# PWR_supply_sch.net
KiCad netlist of a schematic drawn in Altium Designer
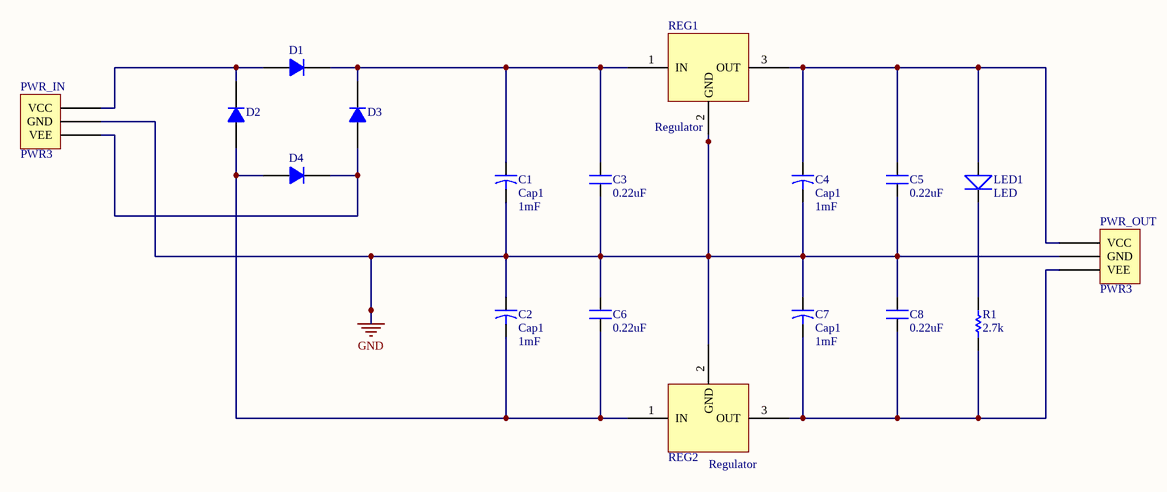
[diagram p0: PWR_supply_sch.SchDoc]

(export (version "E")
  (design (tool "Eeschema 10.0.6"))
  (components
    (comp (ref "C1")
      (value "Cap1")
      (footprint "CAP1")
      (description "Capacitor")
      (fields (field (name "ALTIUM_VALUE") "1mF") (field (name "PUBLISHER") "Altium Limited"))
      (libsource (lib "Common Parts") (part "Cap1"))
    )
    (comp (ref "C2")
      (value "Cap1")
      (footprint "CAP1")
      (description "Capacitor")
      (fields (field (name "ALTIUM_VALUE") "1mF") (field (name "PUBLISHER") "Altium Limited"))
      (libsource (lib "Common Parts") (part "Cap1"))
    )
    (comp (ref "C3")
      (value "0.22uF")
      (footprint "CAP3")
      (description "Capacitor")
      (fields (field (name "Comment") "Cap3") (field (name "PUBLISHER") "Altium Limited"))
      (libsource (lib "Common Parts") (part "Cap3"))
    )
    (comp (ref "C4")
      (value "Cap1")
      (footprint "CAP1")
      (description "Capacitor")
      (fields (field (name "ALTIUM_VALUE") "1mF") (field (name "PUBLISHER") "Altium Limited"))
      (libsource (lib "Common Parts") (part "Cap1"))
    )
    (comp (ref "C5")
      (value "0.22uF")
      (footprint "CAP3")
      (description "Capacitor")
      (fields (field (name "Comment") "Cap3") (field (name "PUBLISHER") "Altium Limited"))
      (libsource (lib "Common Parts") (part "Cap3"))
    )
    (comp (ref "C6")
      (value "0.22uF")
      (footprint "CAP3")
      (description "Capacitor")
      (fields (field (name "Comment") "Cap3") (field (name "PUBLISHER") "Altium Limited"))
      (libsource (lib "Common Parts") (part "Cap3"))
    )
    (comp (ref "C7")
      (value "Cap1")
      (footprint "CAP1")
      (description "Capacitor")
      (fields (field (name "ALTIUM_VALUE") "1mF") (field (name "PUBLISHER") "Altium Limited"))
      (libsource (lib "Common Parts") (part "Cap1"))
    )
    (comp (ref "C8")
      (value "0.22uF")
      (footprint "CAP3")
      (description "Capacitor")
      (fields (field (name "Comment") "Cap3") (field (name "PUBLISHER") "Altium Limited"))
      (libsource (lib "Common Parts") (part "Cap3"))
    )
    (comp (ref "D1")
      (value "1N4007")
      (footprint "1N4007")
      (description "1 Amp General Purpose Rectifier")
      (fields (field (name "PUBLISHER") "Altium Limited"))
      (libsource (lib "Common Parts") (part "1N4007"))
    )
    (comp (ref "D2")
      (value "1N4007")
      (footprint "1N4007")
      (description "1 Amp General Purpose Rectifier")
      (fields (field (name "PUBLISHER") "Altium Limited"))
      (libsource (lib "Common Parts") (part "1N4007"))
    )
    (comp (ref "D3")
      (value "1N4007")
      (footprint "1N4007")
      (description "1 Amp General Purpose Rectifier")
      (fields (field (name "PUBLISHER") "Altium Limited"))
      (libsource (lib "Common Parts") (part "1N4007"))
    )
    (comp (ref "D4")
      (value "1N4007")
      (footprint "1N4007")
      (description "1 Amp General Purpose Rectifier")
      (fields (field (name "PUBLISHER") "Altium Limited"))
      (libsource (lib "Common Parts") (part "1N4007"))
    )
    (comp (ref "LED1") (value "LED") (footprint "LED") (libsource (lib "Common Parts") (part "LED")))
    (comp (ref "PWR_IN") (value "PWR3") (footprint "PWR3") (libsource (lib "") (part "PWR3_1")))
    (comp (ref "PWR_OUT") (value "PWR3") (footprint "PWR3") (libsource (lib "Common Parts") (part "PWR3")))
    (comp (ref "R1")
      (value "2.7k")
      (footprint "RES_TOP_1")
      (description "Resistor")
      (fields (field (name "Comment") "Res1") (field (name "PUBLISHER") "Altium Limited"))
      (libsource (lib "Common Parts") (part "Res1"))
    )
    (comp (ref "REG1") (value "Regulator") (footprint "Regulator") (libsource (lib "") (part "Regulator_1")))
    (comp (ref "REG2")
      (value "Regulator")
      (footprint "Regulator")
      (libsource (lib "Common Parts") (part "Regulator"))
    )
  )
  (nets
    (net (code "1") (name "GND") (class "Default")
      (node (ref "C1") (pin "2") (pinfunction "2_2") (pintype "passive"))
      (node (ref "C2") (pin "1") (pinfunction "1_1") (pintype "passive"))
      (node (ref "C3") (pin "1") (pinfunction "1_1") (pintype "passive"))
      (node (ref "C4") (pin "2") (pinfunction "2_2") (pintype "passive"))
      (node (ref "C5") (pin "1") (pinfunction "1_1") (pintype "passive"))
      (node (ref "C6") (pin "2") (pinfunction "2_2") (pintype "passive"))
      (node (ref "C7") (pin "1") (pinfunction "1_1") (pintype "passive"))
      (node (ref "C8") (pin "2") (pinfunction "2_2") (pintype "passive"))
      (node (ref "PWR_IN") (pin "2") (pinfunction "GND_2") (pintype "passive"))
      (node (ref "PWR_OUT") (pin "2") (pinfunction "GND_2") (pintype "passive"))
      (node (ref "REG1") (pin "2") (pinfunction "GND_2") (pintype "passive"))
      (node (ref "REG2") (pin "2") (pinfunction "GND_2") (pintype "passive"))
    )
    (net (code "2") (name "Net-(D1-A)") (class "Default")
      (node (ref "D1") (pin "1") (pinfunction "A_1") (pintype "passive"))
      (node (ref "D2") (pin "2") (pinfunction "K_2") (pintype "passive"))
      (node (ref "PWR_IN") (pin "1") (pinfunction "VCC_1") (pintype "passive"))
    )
    (net (code "3") (name "Net-(D1-K)") (class "Default")
      (node (ref "C1") (pin "1") (pinfunction "1_1") (pintype "passive"))
      (node (ref "C3") (pin "2") (pinfunction "2_2") (pintype "passive"))
      (node (ref "D1") (pin "2") (pinfunction "K_2") (pintype "passive"))
      (node (ref "D3") (pin "2") (pinfunction "K_2") (pintype "passive"))
      (node (ref "REG1") (pin "1") (pinfunction "IN_1") (pintype "passive"))
    )
    (net (code "4") (name "Net-(D2-A)") (class "Default")
      (node (ref "C2") (pin "2") (pinfunction "2_2") (pintype "passive"))
      (node (ref "C6") (pin "1") (pinfunction "1_1") (pintype "passive"))
      (node (ref "D2") (pin "1") (pinfunction "A_1") (pintype "passive"))
      (node (ref "D4") (pin "1") (pinfunction "A_1") (pintype "passive"))
      (node (ref "REG2") (pin "1") (pinfunction "IN_1") (pintype "passive"))
    )
    (net (code "5") (name "Net-(D3-A)") (class "Default")
      (node (ref "D3") (pin "1") (pinfunction "A_1") (pintype "passive"))
      (node (ref "D4") (pin "2") (pinfunction "K_2") (pintype "passive"))
      (node (ref "PWR_IN") (pin "3") (pinfunction "VEE_3") (pintype "passive"))
    )
    (net (code "6") (name "Net-(LED1-A)") (class "Default")
      (node (ref "C4") (pin "1") (pinfunction "1_1") (pintype "passive"))
      (node (ref "C5") (pin "2") (pinfunction "2_2") (pintype "passive"))
      (node (ref "LED1") (pin "1") (pinfunction "A_1") (pintype "passive"))
      (node (ref "PWR_OUT") (pin "1") (pinfunction "VCC_1") (pintype "passive"))
      (node (ref "REG1") (pin "3") (pinfunction "OUT_3") (pintype "passive"))
    )
    (net (code "7") (name "Net-(LED1-K)") (class "Default")
      (node (ref "LED1") (pin "2") (pinfunction "K_2") (pintype "passive"))
      (node (ref "R1") (pin "2") (pinfunction "2_2") (pintype "passive"))
    )
    (net (code "8") (name "Net-(PWR_OUT-VEE)") (class "Default")
      (node (ref "C7") (pin "2") (pinfunction "2_2") (pintype "passive"))
      (node (ref "C8") (pin "1") (pinfunction "1_1") (pintype "passive"))
      (node (ref "PWR_OUT") (pin "3") (pinfunction "VEE_3") (pintype "passive"))
      (node (ref "R1") (pin "1") (pinfunction "1_1") (pintype "passive"))
      (node (ref "REG2") (pin "3") (pinfunction "OUT_3") (pintype "passive"))
    )
  )
)
